# Breath_LED_Temp_Touch_key_Motor.net
KiCad netlist of a schematic drawn in Altium Designer
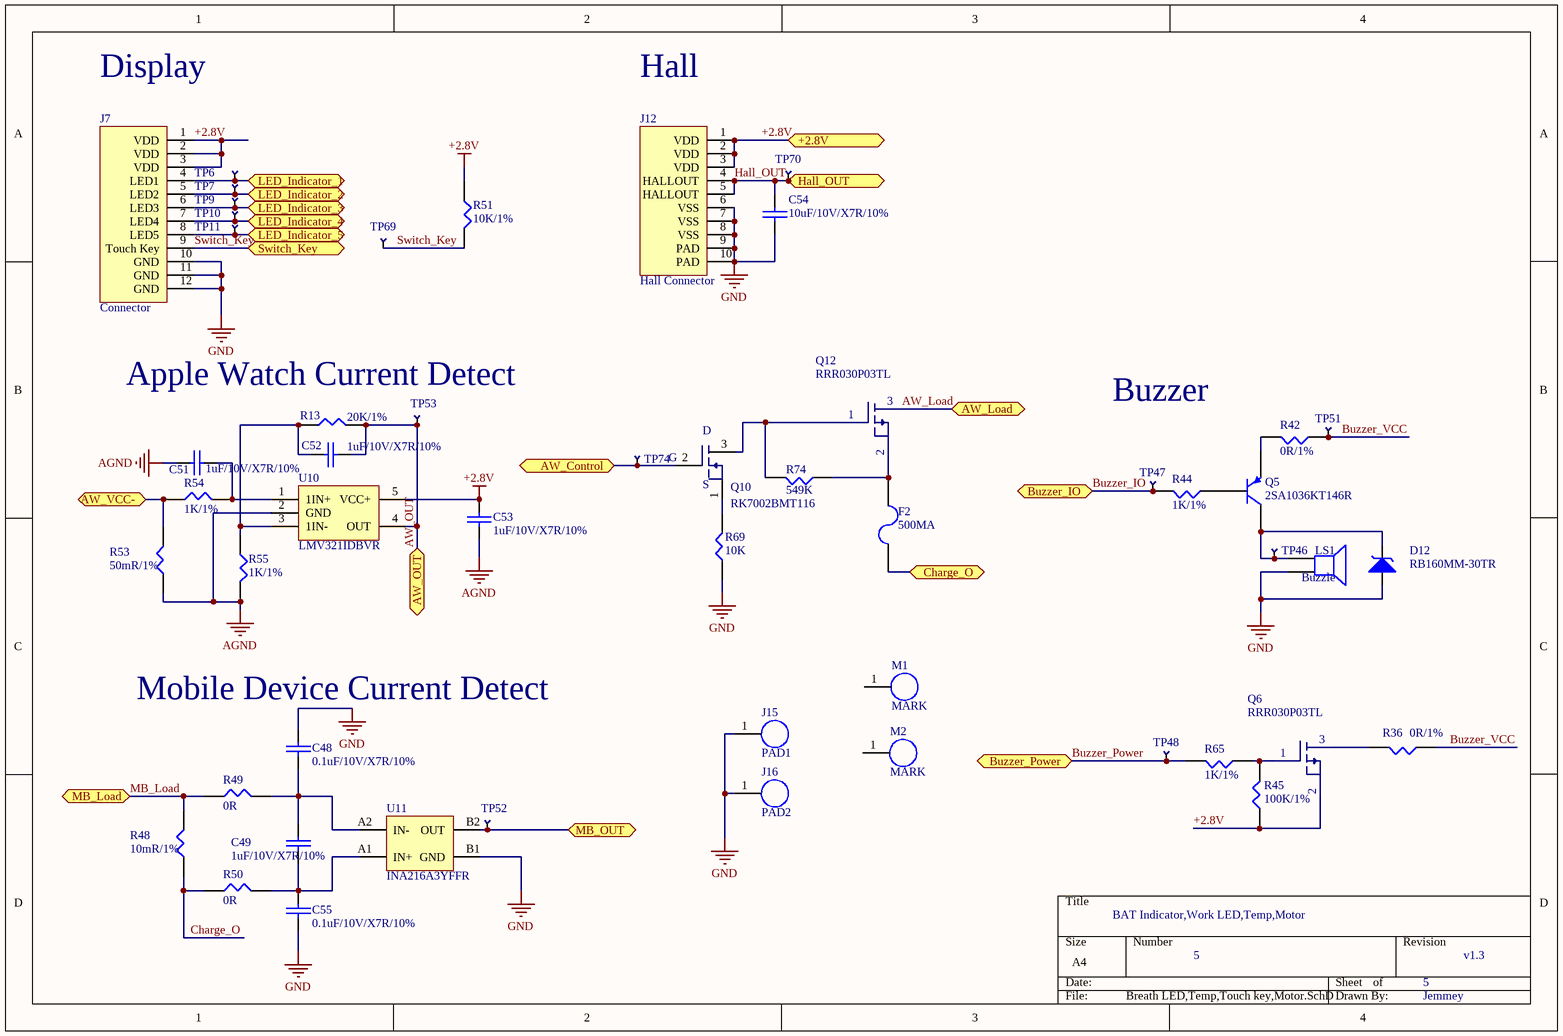
[diagram p0: Breath LED,Temp,Touch key,Motor.SchDoc]

(export (version "E")
  (design (tool "Eeschema 10.0.6"))
  (components
    (comp (ref "C48")
      (value "0.1uF/10V/X7R/10%")
      (footprint "0402C")
      (description "厂家：Murata，型号：GRM155R71A104KA01D")
      (libsource (lib "*") (part "CAP"))
    )
    (comp (ref "C49")
      (value "1uF/10V/X7R/10%")
      (footprint "0402C")
      (description "厂家：Murata，型号：GRM155R61C105KA12D")
      (libsource (lib "*") (part "CAP"))
    )
    (comp (ref "C51")
      (value "1uF/10V/X7R/10%")
      (footprint "0402C")
      (description "厂家：Murata，型号：GRM155R61C105KA12D")
      (libsource (lib "*") (part "CAP"))
    )
    (comp (ref "C52")
      (value "1uF/10V/X7R/10%")
      (footprint "0402C")
      (description "厂家：Murata，型号：GRM155R61C105KA12D")
      (libsource (lib "*") (part "CAP"))
    )
    (comp (ref "C53")
      (value "1uF/10V/X7R/10%")
      (footprint "0402C")
      (description "厂家：Murata，型号：GRM155R61C105KA12D")
      (libsource (lib "*") (part "CAP"))
    )
    (comp (ref "C54")
      (value "10uF/10V/X7R/10%")
      (footprint "0603C")
      (description "厂家：Murata，型号：GRM188R61A106KE69D")
      (libsource (lib "*") (part "CAP"))
    )
    (comp (ref "C55")
      (value "0.1uF/10V/X7R/10%")
      (footprint "0402C")
      (description "厂家：Murata，型号：GRM155R71A104KA01D")
      (libsource (lib "*") (part "CAP"))
    )
    (comp (ref "D12")
      (value "RB160MM-30TR")
      (footprint "DO-214AC")
      (description "厂家：ROHM，型号：RB160MM-30TR")
      (libsource (lib "Moji_Assenbly Test") (part "Schottky barrier rectifier"))
    )
    (comp (ref "F2")
      (value "500MA")
      (footprint "1206-FUSE")
      (description "厂家：万瑞和，型号：WH1206-050")
      (libsource (lib "*") (part "FUSE2"))
    )
    (comp (ref "J7")
      (value "Connector")
      (footprint "FPC_CON12-BACK-MOLEX")
      (description "厂家：Molex，型号：5034801200_sd")
      (libsource (lib "Amber_1") (part "Temp Connector"))
    )
    (comp (ref "J12")
      (value "Hall Connector")
      (description "厂家：京瓷，型号：046298008 000883+")
      (libsource (lib "Amber") (part "Temp Connector"))
    )
    (comp (ref "J15")
      (value "PAD1")
      (footprint "PAD1")
      (description "None")
      (libsource (lib "Amber") (part "PAD1"))
    )
    (comp (ref "J16")
      (value "PAD2")
      (footprint "PAD2")
      (description "None")
      (libsource (lib "Amber") (part "PAD2"))
    )
    (comp (ref "LS1")
      (value "Buzzle")
      (footprint "Buzzer 7525")
      (description "厂家：常州超音电子，型号：SMD-8503-3016-2.7K")
      (libsource (lib "Miscellaneous Devices") (part "Speaker"))
    )
    (comp (ref "M1")
      (value "MARK")
      (footprint "Mark Point")
      (description "None")
      (libsource (lib "Amber") (part "PAD1"))
    )
    (comp (ref "M2")
      (value "MARK")
      (footprint "Mark Point")
      (description "None")
      (libsource (lib "Amber") (part "PAD1"))
    )
    (comp (ref "Q5")
      (value "2SA1036KT146R")
      (footprint "SMT3")
      (description "厂家：ROHM，型号：2SA1036KT146R")
      (libsource (lib "Amber") (part "PNP"))
    )
    (comp (ref "Q6")
      (value "RRR030P03TL")
      (footprint "TSMT3")
      (description "厂家：ROHM，型号：RRR030P03TL")
      (libsource (lib "*") (part "PMOS"))
    )
    (comp (ref "Q10")
      (value "RK7002BMT116")
      (footprint "SOT23")
      (description "厂家：ROHM，型号：RK7002BMT116")
      (libsource (lib "Amber") (part "RK7002BMT116"))
    )
    (comp (ref "Q12")
      (value "RRR030P03TL")
      (footprint "TSMT3")
      (description "厂家：ROHM，型号：RRR030P03TL")
      (libsource (lib "*") (part "PMOS"))
    )
    (comp (ref "R13")
      (value "20K/1%")
      (footprint "0402R")
      (description "厂家：Yageo，型号：RC0402FR-0720KL")
      (libsource (lib "*") (part "RES1"))
    )
    (comp (ref "R36")
      (value "0R/1%")
      (footprint "0603R")
      (description "厂家：Yageo，型号：RC0402FR-070RL")
      (libsource (lib "*") (part "RES1"))
    )
    (comp (ref "R42")
      (value "0R/1%")
      (footprint "0402R")
      (description "厂家：Yageo，型号：RC0402FR-070RL")
      (libsource (lib "*") (part "RES1"))
    )
    (comp (ref "R44")
      (value "1K/1%")
      (footprint "0402R")
      (description "厂家：Yageo，型号：RC0402FR-071KL")
      (libsource (lib "Schlib1") (part "RES"))
    )
    (comp (ref "R45")
      (value "100K/1%")
      (footprint "0402R")
      (description "厂家：Yageo，型号：RC0402FR-07100KL")
      (libsource (lib "Schlib1") (part "RES"))
    )
    (comp (ref "R48")
      (value "10mR/1%")
      (footprint "0805")
      (description "厂家：Yageo，型号：RL0805FR-070R01L")
      (libsource (lib "*") (part "RES1"))
    )
    (comp (ref "R49")
      (value "0R")
      (footprint "0603R")
      (description "厂家：Yageo，型号：RC0603FR-070RL")
      (libsource (lib "*") (part "RES1"))
    )
    (comp (ref "R50")
      (value "0R")
      (footprint "0603R")
      (description "厂家：Yageo，型号：RC0603FR-070RL")
      (libsource (lib "*") (part "RES1"))
    )
    (comp (ref "R51")
      (value "10K/1%")
      (footprint "0402R")
      (description "厂家：Yageo，型号：RC0402FR-0710KL")
      (libsource (lib "*") (part "RES1"))
    )
    (comp (ref "R53")
      (value "50mR/1%")
      (footprint "0805")
      (description "厂家：Yageo，型号：RL0805FR-070R05L")
      (libsource (lib "*") (part "RES1"))
    )
    (comp (ref "R54")
      (value "1K/1%")
      (footprint "0402R")
      (description "厂家：Yageo，型号：RC0402FR-071KL")
      (libsource (lib "*") (part "RES1"))
    )
    (comp (ref "R55")
      (value "1K/1%")
      (footprint "0402R")
      (description "厂家：Yageo，型号：RC0402FR-071KL")
      (libsource (lib "*") (part "RES1"))
    )
    (comp (ref "R65")
      (value "1K/1%")
      (footprint "0402R")
      (description "厂家：Yageo，型号：RC0402FR-071KL")
      (libsource (lib "Schlib1") (part "RES"))
    )
    (comp (ref "R69") (value "10K") (footprint "0402R") (libsource (lib "*") (part "RES1")))
    (comp (ref "R74") (value "549K") (footprint "0402R") (libsource (lib "*") (part "RES1")))
    (comp (ref "TP6")
      (value "TEST")
      (footprint "Test Pad")
      (description "Test Point")
      (libsource (lib "Amber") (part "TEST"))
    )
    (comp (ref "TP7")
      (value "TEST")
      (footprint "Test Pad")
      (description "Test Point")
      (libsource (lib "Amber") (part "TEST"))
    )
    (comp (ref "TP9")
      (value "TEST")
      (footprint "Test Pad")
      (description "Test Point")
      (libsource (lib "Amber") (part "TEST"))
    )
    (comp (ref "TP10")
      (value "TEST")
      (footprint "Test Pad")
      (description "Test Point")
      (libsource (lib "Amber") (part "TEST"))
    )
    (comp (ref "TP11")
      (value "TEST")
      (footprint "Test Pad")
      (description "Test Point")
      (libsource (lib "Amber") (part "TEST"))
    )
    (comp (ref "TP46")
      (value "TEST")
      (footprint "Test Pad")
      (description "Test Point")
      (libsource (lib "Amber") (part "TEST"))
    )
    (comp (ref "TP47")
      (value "TEST")
      (footprint "Test Pad")
      (description "Test Point")
      (libsource (lib "Amber") (part "TEST"))
    )
    (comp (ref "TP48")
      (value "TEST")
      (footprint "Test Pad")
      (description "Test Point")
      (libsource (lib "Amber") (part "TEST"))
    )
    (comp (ref "TP51")
      (value "TEST")
      (footprint "Test Pad")
      (description "Test Point")
      (libsource (lib "Amber") (part "TEST"))
    )
    (comp (ref "TP52")
      (value "TEST")
      (footprint "Test Pad")
      (description "Test Point")
      (libsource (lib "Amber") (part "TEST"))
    )
    (comp (ref "TP53")
      (value "TEST")
      (footprint "Test Pad")
      (description "Test Point")
      (libsource (lib "Amber") (part "TEST"))
    )
    (comp (ref "TP69")
      (value "TEST")
      (footprint "Test Pad")
      (description "Test Point")
      (libsource (lib "Amber") (part "TEST"))
    )
    (comp (ref "TP70")
      (value "TEST")
      (footprint "Test Pad")
      (description "Test Point")
      (libsource (lib "Amber") (part "TEST"))
    )
    (comp (ref "TP74")
      (value "TEST")
      (footprint "Test Pad")
      (libsource (lib "LED Front Panel Connectboard(20141126)") (part "TEST"))
    )
    (comp (ref "U10")
      (value "LMV321IDBVR")
      (description "厂家：TI，型号：LMV321IDBVR")
      (libsource (lib "Amber_Main_Board_1") (part "LMV321IDBVR"))
    )
    (comp (ref "U11")
      (value "INA216A3YFFR")
      (footprint "YFF")
      (description "厂家：TI，型号：INA216A3YFFR")
      (libsource (lib "Amber") (part "INA216A3YFFR"))
    )
  )
  (nets
    (net (code "1") (name "+2.8V") (class "Default")
      (node (ref "C53") (pin "2") (pinfunction "2_2") (pintype "passive"))
      (node (ref "J12") (pin "1") (pinfunction "VDD_1") (pintype "passive"))
      (node (ref "J12") (pin "2") (pinfunction "VDD_2") (pintype "passive"))
      (node (ref "J12") (pin "3") (pinfunction "VDD_3") (pintype "passive"))
      (node (ref "J7") (pin "1") (pinfunction "VDD_1") (pintype "passive"))
      (node (ref "J7") (pin "2") (pinfunction "VDD_2") (pintype "passive"))
      (node (ref "J7") (pin "3") (pinfunction "VDD_3") (pintype "passive"))
      (node (ref "Q6") (pin "2") (pinfunction "S_2") (pintype "passive"))
      (node (ref "R45") (pin "1") (pinfunction "1_1") (pintype "passive"))
      (node (ref "R51") (pin "1") (pinfunction "1_1") (pintype "passive"))
      (node (ref "U10") (pin "5") (pinfunction "VCC+_5") (pintype "passive"))
    )
    (net (code "2") (name "/AW_Control") (class "Default")
      (node (ref "Q10") (pin "2") (pinfunction "G_2") (pintype "passive"))
      (node (ref "TP74") (pin "1") (pinfunction "1_1") (pintype "passive"))
    )
    (net (code "3") (name "/AW_Load") (class "Default")
      (node (ref "Q12") (pin "3") (pinfunction "D_3") (pintype "passive"))
    )
    (net (code "4") (name "/AW_OUT") (class "Default")
      (node (ref "C52") (pin "2") (pinfunction "2_2") (pintype "passive"))
      (node (ref "R13") (pin "2") (pinfunction "2_2") (pintype "passive"))
      (node (ref "TP53") (pin "1") (pinfunction "1_1") (pintype "passive"))
      (node (ref "U10") (pin "4") (pinfunction "OUT_4") (pintype "passive"))
    )
    (net (code "5") (name "/AW_VCC-") (class "Default")
      (node (ref "R53") (pin "2") (pinfunction "2_2") (pintype "passive"))
      (node (ref "R54") (pin "1") (pinfunction "1_1") (pintype "passive"))
    )
    (net (code "6") (name "/Buzzer_IO") (class "Default")
      (node (ref "R44") (pin "2") (pinfunction "2_2") (pintype "passive"))
      (node (ref "TP47") (pin "1") (pinfunction "1_1") (pintype "passive"))
    )
    (net (code "7") (name "/Buzzer_Power") (class "Default")
      (node (ref "R65") (pin "2") (pinfunction "2_2") (pintype "passive"))
      (node (ref "TP48") (pin "1") (pinfunction "1_1") (pintype "passive"))
    )
    (net (code "8") (name "/Buzzer_VCC") (class "Default")
      (node (ref "R36") (pin "1") (pinfunction "1_1") (pintype "passive"))
      (node (ref "R42") (pin "1") (pinfunction "1_1") (pintype "passive"))
      (node (ref "TP51") (pin "1") (pinfunction "1_1") (pintype "passive"))
    )
    (net (code "9") (name "/Charge_O") (class "Default")
      (node (ref "F2") (pin "2") (pinfunction "2_2") (pintype "passive"))
      (node (ref "R48") (pin "1") (pinfunction "1_1") (pintype "passive"))
      (node (ref "R50") (pin "1") (pinfunction "1_1") (pintype "passive"))
    )
    (net (code "10") (name "/Hall_OUT") (class "Default")
      (node (ref "C54") (pin "1") (pinfunction "1_1") (pintype "passive"))
      (node (ref "J12") (pin "4") (pinfunction "HALLOUT_4") (pintype "passive"))
      (node (ref "J12") (pin "5") (pinfunction "HALLOUT_5") (pintype "passive"))
      (node (ref "TP70") (pin "1") (pinfunction "1_1") (pintype "passive"))
    )
    (net (code "11") (name "/LED_Indicator_1") (class "Default")
      (node (ref "J7") (pin "4") (pinfunction "LED1_4") (pintype "passive"))
      (node (ref "TP6") (pin "1") (pinfunction "1_1") (pintype "passive"))
    )
    (net (code "12") (name "/LED_Indicator_2") (class "Default")
      (node (ref "J7") (pin "5") (pinfunction "LED2_5") (pintype "passive"))
      (node (ref "TP7") (pin "1") (pinfunction "1_1") (pintype "passive"))
    )
    (net (code "13") (name "/LED_Indicator_3") (class "Default")
      (node (ref "J7") (pin "6") (pinfunction "LED3_6") (pintype "passive"))
      (node (ref "TP9") (pin "1") (pinfunction "1_1") (pintype "passive"))
    )
    (net (code "14") (name "/LED_Indicator_4") (class "Default")
      (node (ref "J7") (pin "7") (pinfunction "LED4_7") (pintype "passive"))
      (node (ref "TP10") (pin "1") (pinfunction "1_1") (pintype "passive"))
    )
    (net (code "15") (name "/LED_Indicator_5") (class "Default")
      (node (ref "J7") (pin "8") (pinfunction "LED5_8") (pintype "passive"))
      (node (ref "TP11") (pin "1") (pinfunction "1_1") (pintype "passive"))
    )
    (net (code "16") (name "/MB_Load") (class "Default")
      (node (ref "R48") (pin "2") (pinfunction "2_2") (pintype "passive"))
      (node (ref "R49") (pin "1") (pinfunction "1_1") (pintype "passive"))
    )
    (net (code "17") (name "/MB_OUT") (class "Default")
      (node (ref "TP52") (pin "1") (pinfunction "1_1") (pintype "passive"))
      (node (ref "U11") (pin "B2") (pinfunction "OUT_B2") (pintype "passive"))
    )
    (net (code "18") (name "/Switch_Key") (class "Default")
      (node (ref "J7") (pin "9") (pinfunction "Touch_Key_9") (pintype "passive"))
      (node (ref "R51") (pin "2") (pinfunction "2_2") (pintype "passive"))
      (node (ref "TP69") (pin "1") (pinfunction "1_1") (pintype "passive"))
    )
    (net (code "19") (name "AGND") (class "Default")
      (node (ref "C51") (pin "1") (pinfunction "1_1") (pintype "passive"))
      (node (ref "C53") (pin "1") (pinfunction "1_1") (pintype "passive"))
      (node (ref "R53") (pin "1") (pinfunction "1_1") (pintype "passive"))
      (node (ref "R55") (pin "2") (pinfunction "2_2") (pintype "passive"))
      (node (ref "U10") (pin "2") (pinfunction "GND_2") (pintype "passive"))
    )
    (net (code "20") (name "GND") (class "Default")
      (node (ref "C48") (pin "1") (pinfunction "1_1") (pintype "passive"))
      (node (ref "C54") (pin "2") (pinfunction "2_2") (pintype "passive"))
      (node (ref "C55") (pin "2") (pinfunction "2_2") (pintype "passive"))
      (node (ref "D12") (pin "2") (pinfunction "A_2") (pintype "passive"))
      (node (ref "J12") (pin "10") (pinfunction "PAD_10") (pintype "passive"))
      (node (ref "J12") (pin "6") (pinfunction "VSS_6") (pintype "passive"))
      (node (ref "J12") (pin "7") (pinfunction "VSS_7") (pintype "passive"))
      (node (ref "J12") (pin "8") (pinfunction "VSS_8") (pintype "passive"))
      (node (ref "J12") (pin "9") (pinfunction "PAD_9") (pintype "passive"))
      (node (ref "J15") (pin "1") (pinfunction "1_1") (pintype "passive"))
      (node (ref "J16") (pin "1") (pinfunction "1_1") (pintype "passive"))
      (node (ref "J7") (pin "10") (pinfunction "GND_10") (pintype "passive"))
      (node (ref "J7") (pin "11") (pinfunction "GND_11") (pintype "passive"))
      (node (ref "J7") (pin "12") (pinfunction "GND_12") (pintype "passive"))
      (node (ref "LS1") (pin "2") (pinfunction "2_2") (pintype "passive"))
      (node (ref "R69") (pin "1") (pinfunction "1_1") (pintype "passive"))
      (node (ref "U11") (pin "B1") (pinfunction "GND_B1") (pintype "passive"))
    )
    (net (code "21") (name "Net-(D12-K)") (class "Default")
      (node (ref "D12") (pin "1") (pinfunction "K_1") (pintype "passive"))
      (node (ref "LS1") (pin "1") (pinfunction "1_1") (pintype "passive"))
      (node (ref "Q5") (pin "1") (pinfunction "E_1") (pintype "passive"))
      (node (ref "TP46") (pin "1") (pinfunction "1_1") (pintype "passive"))
    )
    (net (code "22") (name "Net-(Q5-B)") (class "Default")
      (node (ref "Q5") (pin "2") (pinfunction "B_2") (pintype "passive"))
      (node (ref "R44") (pin "1") (pinfunction "1_1") (pintype "passive"))
    )
    (net (code "23") (name "Net-(Q5-C)") (class "Default")
      (node (ref "Q5") (pin "3") (pinfunction "C_3") (pintype "passive"))
      (node (ref "R42") (pin "2") (pinfunction "2_2") (pintype "passive"))
    )
    (net (code "24") (name "Net-(Q6-D)") (class "Default")
      (node (ref "Q6") (pin "3") (pinfunction "D_3") (pintype "passive"))
      (node (ref "R36") (pin "2") (pinfunction "2_2") (pintype "passive"))
    )
    (net (code "25") (name "Net-(Q6-G)") (class "Default")
      (node (ref "Q6") (pin "1") (pinfunction "G_1") (pintype "passive"))
      (node (ref "R45") (pin "2") (pinfunction "2_2") (pintype "passive"))
      (node (ref "R65") (pin "1") (pinfunction "1_1") (pintype "passive"))
    )
    (net (code "26") (name "Net-(Q10-D)") (class "Default")
      (node (ref "Q10") (pin "3") (pinfunction "D_3") (pintype "passive"))
      (node (ref "Q12") (pin "1") (pinfunction "G_1") (pintype "passive"))
      (node (ref "R74") (pin "2") (pinfunction "2_2") (pintype "passive"))
    )
    (net (code "27") (name "Net-(Q10-S)") (class "Default")
      (node (ref "Q10") (pin "1") (pinfunction "S_1") (pintype "passive"))
      (node (ref "R69") (pin "2") (pinfunction "2_2") (pintype "passive"))
    )
    (net (code "28") (name "Net-(Q12-S)") (class "Default")
      (node (ref "F2") (pin "1") (pinfunction "1_1") (pintype "passive"))
      (node (ref "Q12") (pin "2") (pinfunction "S_2") (pintype "passive"))
      (node (ref "R74") (pin "1") (pinfunction "1_1") (pintype "passive"))
    )
    (net (code "29") (name "Net-(U10-1IN+)") (class "Default")
      (node (ref "C51") (pin "2") (pinfunction "2_2") (pintype "passive"))
      (node (ref "R54") (pin "2") (pinfunction "2_2") (pintype "passive"))
      (node (ref "U10") (pin "1") (pinfunction "1IN+_1") (pintype "passive"))
    )
    (net (code "30") (name "Net-(U10-1IN-)") (class "Default")
      (node (ref "C52") (pin "1") (pinfunction "1_1") (pintype "passive"))
      (node (ref "R13") (pin "1") (pinfunction "1_1") (pintype "passive"))
      (node (ref "R55") (pin "1") (pinfunction "1_1") (pintype "passive"))
      (node (ref "U10") (pin "3") (pinfunction "1IN-_3") (pintype "passive"))
    )
    (net (code "31") (name "Net-(U11-IN+)") (class "Default")
      (node (ref "C49") (pin "2") (pinfunction "2_2") (pintype "passive"))
      (node (ref "C55") (pin "1") (pinfunction "1_1") (pintype "passive"))
      (node (ref "R50") (pin "2") (pinfunction "2_2") (pintype "passive"))
      (node (ref "U11") (pin "A1") (pinfunction "IN+_A1") (pintype "passive"))
    )
    (net (code "32") (name "Net-(U11-IN-)") (class "Default")
      (node (ref "C48") (pin "2") (pinfunction "2_2") (pintype "passive"))
      (node (ref "C49") (pin "1") (pinfunction "1_1") (pintype "passive"))
      (node (ref "R49") (pin "2") (pinfunction "2_2") (pintype "passive"))
      (node (ref "U11") (pin "A2") (pinfunction "IN-_A2") (pintype "passive"))
    )
    (net (code "33") (name "unconnected-(M1-Pad1)") (class "Default")
      (node (ref "M1") (pin "1") (pinfunction "1_1") (pintype "passive"))
    )
    (net (code "34") (name "unconnected-(M2-Pad1)") (class "Default")
      (node (ref "M2") (pin "1") (pinfunction "1_1") (pintype "passive"))
    )
  )
)
